# Filter_Capacitors_-_Port_K.net
KiCad netlist of a schematic drawn in Altium Designer
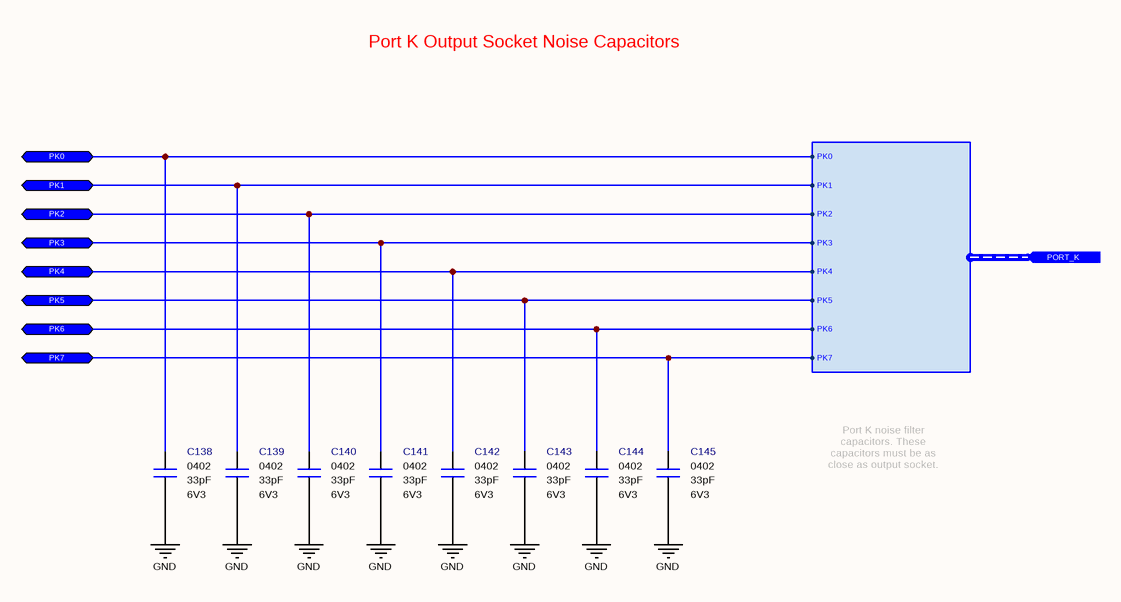
[diagram p0: Filter Capacitors - Port K.SchDoc]

(export (version "E")
  (design (tool "Eeschema 10.0.6"))
  (components
    (comp (ref "C138")
      (value "33pF")
      (footprint "CAPACITOR_0402")
      (description "Capacitor - 33pF [0402] (Ceramic)")
      (fields
        (field (name "TOLERANCE") "10%")
        (field (name "CASE") "0402")
        (field (name "VOLTAGE") "6V3")
        (field (name "MANUFACTURER PART NUMBER") "C0402C330J9RACAUTO")
      )
      (libsource (lib "Ovoo_Library") (part "Capacitor - 33pF [0402-6V3]"))
    )
    (comp (ref "C139")
      (value "33pF")
      (footprint "CAPACITOR_0402")
      (description "Capacitor - 33pF [0402] (Ceramic)")
      (fields
        (field (name "TOLERANCE") "10%")
        (field (name "CASE") "0402")
        (field (name "VOLTAGE") "6V3")
        (field (name "MANUFACTURER PART NUMBER") "C0402C330J9RACAUTO")
      )
      (libsource (lib "Ovoo_Library") (part "Capacitor - 33pF [0402-6V3]"))
    )
    (comp (ref "C140")
      (value "33pF")
      (footprint "CAPACITOR_0402")
      (description "Capacitor - 33pF [0402] (Ceramic)")
      (fields
        (field (name "TOLERANCE") "10%")
        (field (name "CASE") "0402")
        (field (name "VOLTAGE") "6V3")
        (field (name "MANUFACTURER PART NUMBER") "C0402C330J9RACAUTO")
      )
      (libsource (lib "Ovoo_Library") (part "Capacitor - 33pF [0402-6V3]"))
    )
    (comp (ref "C141")
      (value "33pF")
      (footprint "CAPACITOR_0402")
      (description "Capacitor - 33pF [0402] (Ceramic)")
      (fields
        (field (name "TOLERANCE") "10%")
        (field (name "CASE") "0402")
        (field (name "VOLTAGE") "6V3")
        (field (name "MANUFACTURER PART NUMBER") "C0402C330J9RACAUTO")
      )
      (libsource (lib "Ovoo_Library") (part "Capacitor - 33pF [0402-6V3]"))
    )
    (comp (ref "C142")
      (value "33pF")
      (footprint "CAPACITOR_0402")
      (description "Capacitor - 33pF [0402] (Ceramic)")
      (fields
        (field (name "TOLERANCE") "10%")
        (field (name "CASE") "0402")
        (field (name "VOLTAGE") "6V3")
        (field (name "MANUFACTURER PART NUMBER") "C0402C330J9RACAUTO")
      )
      (libsource (lib "Ovoo_Library") (part "Capacitor - 33pF [0402-6V3]"))
    )
    (comp (ref "C143")
      (value "33pF")
      (footprint "CAPACITOR_0402")
      (description "Capacitor - 33pF [0402] (Ceramic)")
      (fields
        (field (name "TOLERANCE") "10%")
        (field (name "CASE") "0402")
        (field (name "VOLTAGE") "6V3")
        (field (name "MANUFACTURER PART NUMBER") "C0402C330J9RACAUTO")
      )
      (libsource (lib "Ovoo_Library") (part "Capacitor - 33pF [0402-6V3]"))
    )
    (comp (ref "C144")
      (value "33pF")
      (footprint "CAPACITOR_0402")
      (description "Capacitor - 33pF [0402] (Ceramic)")
      (fields
        (field (name "TOLERANCE") "10%")
        (field (name "CASE") "0402")
        (field (name "VOLTAGE") "6V3")
        (field (name "MANUFACTURER PART NUMBER") "C0402C330J9RACAUTO")
      )
      (libsource (lib "Ovoo_Library") (part "Capacitor - 33pF [0402-6V3]"))
    )
    (comp (ref "C145")
      (value "33pF")
      (footprint "CAPACITOR_0402")
      (description "Capacitor - 33pF [0402] (Ceramic)")
      (fields
        (field (name "TOLERANCE") "10%")
        (field (name "CASE") "0402")
        (field (name "VOLTAGE") "6V3")
        (field (name "MANUFACTURER PART NUMBER") "C0402C330J9RACAUTO")
      )
      (libsource (lib "Ovoo_Library") (part "Capacitor - 33pF [0402-6V3]"))
    )
  )
  (nets
    (net (code "2") (name "/PK0") (class "Default")
      (node (ref "C138") (pin "2") (pinfunction "2_2") (pintype "passive"))
    )
    (net (code "3") (name "/PK1") (class "Default")
      (node (ref "C139") (pin "2") (pinfunction "2_2") (pintype "passive"))
    )
    (net (code "4") (name "/PK2") (class "Default")
      (node (ref "C140") (pin "2") (pinfunction "2_2") (pintype "passive"))
    )
    (net (code "5") (name "/PK3") (class "Default")
      (node (ref "C141") (pin "2") (pinfunction "2_2") (pintype "passive"))
    )
    (net (code "6") (name "/PK4") (class "Default")
      (node (ref "C142") (pin "2") (pinfunction "2_2") (pintype "passive"))
    )
    (net (code "7") (name "/PK5") (class "Default")
      (node (ref "C143") (pin "2") (pinfunction "2_2") (pintype "passive"))
    )
    (net (code "8") (name "/PK6") (class "Default")
      (node (ref "C144") (pin "2") (pinfunction "2_2") (pintype "passive"))
    )
    (net (code "9") (name "/PK7") (class "Default")
      (node (ref "C145") (pin "2") (pinfunction "2_2") (pintype "passive"))
    )
    (net (code "11") (name "GND") (class "Default")
      (node (ref "C138") (pin "1") (pinfunction "1_1") (pintype "passive"))
      (node (ref "C139") (pin "1") (pinfunction "1_1") (pintype "passive"))
      (node (ref "C140") (pin "1") (pinfunction "1_1") (pintype "passive"))
      (node (ref "C141") (pin "1") (pinfunction "1_1") (pintype "passive"))
      (node (ref "C142") (pin "1") (pinfunction "1_1") (pintype "passive"))
      (node (ref "C143") (pin "1") (pinfunction "1_1") (pintype "passive"))
      (node (ref "C144") (pin "1") (pinfunction "1_1") (pintype "passive"))
      (node (ref "C145") (pin "1") (pinfunction "1_1") (pintype "passive"))
    )
  )
)
